# RS232.net
KiCad netlist of a schematic drawn in Altium Designer
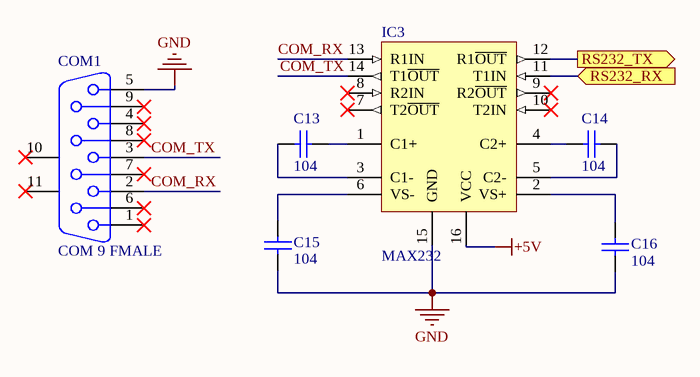
[diagram p0: RS232.SchDoc]

(export (version "E")
  (design (tool "Eeschema 10.0.6"))
  (components
    (comp (ref "C13")
      (value "104")
      (footprint "tu 0805")
      (description "Dán")
      (libsource (lib "Altium_Lib_by_KhueNguyenCreator") (part "Tu 0805 104 50V 10%"))
    )
    (comp (ref "C14")
      (value "104")
      (footprint "tu 0805")
      (description "Dán")
      (libsource (lib "Altium_Lib_by_KhueNguyenCreator") (part "Tu 0805 104 50V 10%"))
    )
    (comp (ref "C15")
      (value "104")
      (footprint "tu 0805")
      (description "Dán")
      (libsource (lib "Altium_Lib_by_KhueNguyenCreator") (part "Tu 0805 104 50V 10%"))
    )
    (comp (ref "C16")
      (value "104")
      (footprint "tu 0805")
      (description "Dán")
      (libsource (lib "Altium_Lib_by_KhueNguyenCreator") (part "Tu 0805 104 50V 10%"))
    )
    (comp (ref "COM1")
      (value "COM 9 FMALE")
      (footprint "DSB 9-F")
      (description "COM 9")
      (fields (field (name "PUBLISHER") "Altium Limited"))
      (libsource (lib "syhaunguyen") (part "DSB9F"))
    )
    (comp (ref "IC3")
      (value "MAX232")
      (footprint "SO-G16")
      (description "Dual EIA-232 Driver/Receiver")
      (libsource (lib "syhaunguyen") (part "MAX232"))
    )
  )
  (nets
    (net (code "1") (name "+5V") (class "Default")
      (node (ref "IC3") (pin "16") (pinfunction "VCC_16") (pintype "power_in"))
    )
    (net (code "2") (name "/COM_RX") (class "Default")
      (node (ref "COM1") (pin "2") (pinfunction "2_2") (pintype "passive"))
      (node (ref "IC3") (pin "13") (pinfunction "R1IN_13") (pintype "input"))
    )
    (net (code "3") (name "/COM_TX") (class "Default")
      (node (ref "COM1") (pin "3") (pinfunction "3_3") (pintype "passive"))
      (node (ref "IC3") (pin "14") (pinfunction "T1~{OUT}_14") (pintype "output"))
    )
    (net (code "4") (name "/RS232_RX") (class "Default")
      (node (ref "IC3") (pin "11") (pinfunction "T1IN_11") (pintype "input"))
    )
    (net (code "5") (name "/RS232_TX") (class "Default")
      (node (ref "IC3") (pin "12") (pinfunction "R1~{OUT}_12") (pintype "output"))
    )
    (net (code "6") (name "GND") (class "Default")
      (node (ref "C15") (pin "2") (pinfunction "2_2") (pintype "passive"))
      (node (ref "C16") (pin "2") (pinfunction "2_2") (pintype "passive"))
      (node (ref "COM1") (pin "5") (pinfunction "5_5") (pintype "passive"))
      (node (ref "IC3") (pin "15") (pinfunction "GND_15") (pintype "power_in"))
    )
    (net (code "7") (name "Net-(IC3-C1+)") (class "Default")
      (node (ref "C13") (pin "2") (pinfunction "2_2") (pintype "passive"))
      (node (ref "IC3") (pin "1") (pinfunction "C1+_1") (pintype "passive"))
    )
    (net (code "8") (name "Net-(IC3-C1-)") (class "Default")
      (node (ref "C13") (pin "1") (pinfunction "1_1") (pintype "passive"))
      (node (ref "IC3") (pin "3") (pinfunction "C1-_3") (pintype "passive"))
    )
    (net (code "9") (name "Net-(IC3-C2+)") (class "Default")
      (node (ref "C14") (pin "2") (pinfunction "2_2") (pintype "passive"))
      (node (ref "IC3") (pin "4") (pinfunction "C2+_4") (pintype "passive"))
    )
    (net (code "10") (name "Net-(IC3-C2-)") (class "Default")
      (node (ref "C14") (pin "1") (pinfunction "1_1") (pintype "passive"))
      (node (ref "IC3") (pin "5") (pinfunction "C2-_5") (pintype "passive"))
    )
    (net (code "11") (name "Net-(IC3-VS+)") (class "Default")
      (node (ref "C16") (pin "1") (pinfunction "1_1") (pintype "passive"))
      (node (ref "IC3") (pin "2") (pinfunction "VS+_2") (pintype "power_in"))
    )
    (net (code "12") (name "Net-(IC3-VS-)") (class "Default")
      (node (ref "C15") (pin "1") (pinfunction "1_1") (pintype "passive"))
      (node (ref "IC3") (pin "6") (pinfunction "VS-_6") (pintype "power_in"))
    )
    (net (code "13") (name "unconnected-(COM1-MH1-Pad10)") (class "Default")
      (node (ref "COM1") (pin "10") (pinfunction "MH1_10") (pintype "passive+no_connect"))
    )
    (net (code "14") (name "unconnected-(COM1-MH2-Pad11)") (class "Default")
      (node (ref "COM1") (pin "11") (pinfunction "MH2_11") (pintype "passive+no_connect"))
    )
    (net (code "15") (name "unconnected-(COM1-Pad1)") (class "Default")
      (node (ref "COM1") (pin "1") (pinfunction "1_1") (pintype "passive+no_connect"))
    )
    (net (code "16") (name "unconnected-(COM1-Pad4)") (class "Default")
      (node (ref "COM1") (pin "4") (pinfunction "4_4") (pintype "passive+no_connect"))
    )
    (net (code "17") (name "unconnected-(COM1-Pad6)") (class "Default")
      (node (ref "COM1") (pin "6") (pinfunction "6_6") (pintype "passive+no_connect"))
    )
    (net (code "18") (name "unconnected-(COM1-Pad7)") (class "Default")
      (node (ref "COM1") (pin "7") (pinfunction "7_7") (pintype "passive+no_connect"))
    )
    (net (code "19") (name "unconnected-(COM1-Pad8)") (class "Default")
      (node (ref "COM1") (pin "8") (pinfunction "8_8") (pintype "passive+no_connect"))
    )
    (net (code "20") (name "unconnected-(COM1-Pad9)") (class "Default")
      (node (ref "COM1") (pin "9") (pinfunction "9_9") (pintype "passive+no_connect"))
    )
    (net (code "21") (name "unconnected-(IC3-R2IN-Pad8)") (class "Default")
      (node (ref "IC3") (pin "8") (pinfunction "R2IN_8") (pintype "input+no_connect"))
    )
    (net (code "22") (name "unconnected-(IC3-R2~{OUT}-Pad9)") (class "Default")
      (node (ref "IC3") (pin "9") (pinfunction "R2~{OUT}_9") (pintype "output+no_connect"))
    )
    (net (code "23") (name "unconnected-(IC3-T2IN-Pad10)") (class "Default")
      (node (ref "IC3") (pin "10") (pinfunction "T2IN_10") (pintype "input+no_connect"))
    )
    (net (code "24") (name "unconnected-(IC3-T2~{OUT}-Pad7)") (class "Default")
      (node (ref "IC3") (pin "7") (pinfunction "T2~{OUT}_7") (pintype "output+no_connect"))
    )
  )
)
